# Lab_5_4.net
KiCad netlist of a schematic drawn in EAGLE
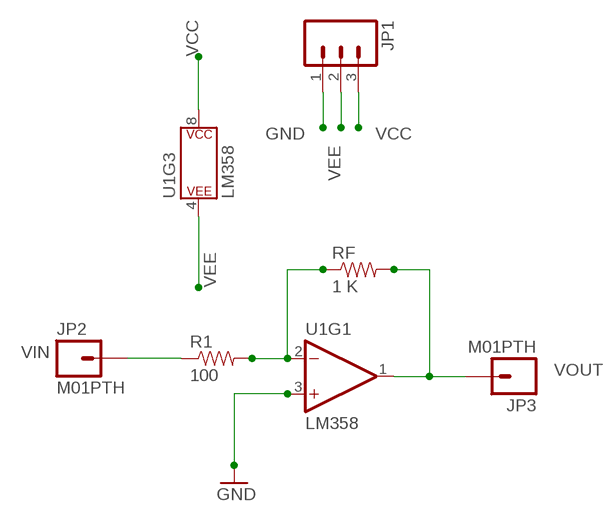
[diagram p0: schematic, sheet 1]

(export (version "E")
  (design (tool "Eeschema 10.0.6"))
  (components
    (comp (ref "JP1")
      (value "M03LOCK")
      (footprint "eagle-import:1X03_LOCK")
      (libsource (lib "eagle-import") (part "M03LOCK"))
    )
    (comp (ref "JP2")
      (value "M01PTH")
      (footprint "eagle-import:1X01")
      (libsource (lib "eagle-import") (part "M01PTH"))
    )
    (comp (ref "JP3")
      (value "M01PTH")
      (footprint "eagle-import:1X01")
      (libsource (lib "eagle-import") (part "M01PTH"))
    )
    (comp (ref "R1")
      (value "100")
      (footprint "eagle-import:1206")
      (libsource (lib "eagle-import") (part "RESISTOR1206"))
    )
    (comp (ref "RF")
      (value "1 K")
      (footprint "eagle-import:1206")
      (libsource (lib "eagle-import") (part "RESISTOR1206"))
    )
    (comp (ref "U1")
      (value "LM358")
      (footprint "eagle-import:DIP08-KIT")
      (libsource (lib "eagle-import") (part "LM358KIT"))
    )
  )
  (nets
    (net (code "1") (name "/VCC") (class "Default")
      (node (ref "JP1") (pin "3") (pinfunction "3_3") (pintype "passive"))
      (node (ref "U1") (pin "8") (pinfunction "P$V+_8") (pintype "bidirectional"))
    )
    (net (code "2") (name "/VEE") (class "Default")
      (node (ref "JP1") (pin "2") (pinfunction "2_2") (pintype "passive"))
      (node (ref "U1") (pin "4") (pinfunction "P$V-_4") (pintype "bidirectional"))
    )
    (net (code "3") (name "/VIN") (class "Default")
      (node (ref "JP2") (pin "1") (pinfunction "1_1") (pintype "passive"))
      (node (ref "R1") (pin "1") (pinfunction "1_1") (pintype "passive"))
    )
    (net (code "4") (name "/VOUT") (class "Default")
      (node (ref "JP3") (pin "1") (pinfunction "1_1") (pintype "passive"))
      (node (ref "RF") (pin "2") (pinfunction "2_2") (pintype "passive"))
      (node (ref "U1") (pin "1") (pinfunction "OUT_1") (pintype "output"))
    )
    (net (code "5") (name "GND") (class "Default")
      (node (ref "JP1") (pin "1") (pinfunction "1_1") (pintype "passive"))
      (node (ref "U1") (pin "3") (pinfunction "+IN_3") (pintype "input"))
    )
    (net (code "6") (name "Net-(U1A--IN)") (class "Default")
      (node (ref "R1") (pin "2") (pinfunction "2_2") (pintype "passive"))
      (node (ref "RF") (pin "1") (pinfunction "1_1") (pintype "passive"))
      (node (ref "U1") (pin "2") (pinfunction "-IN_2") (pintype "input"))
    )
  )
)
